# tssop38.net
KiCad netlist of a schematic drawn in EAGLE
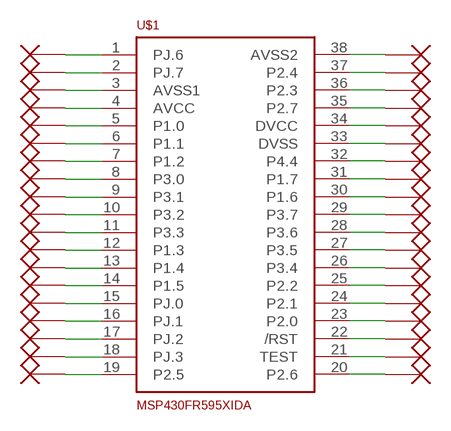
[diagram p0: schematic, sheet 1]

(export (version "E")
  (design (tool "Eeschema 10.0.6"))
  (components
    (comp (ref "P1")
      (value "PIN")
      (footprint "eagle-import:PIN")
      (libsource (lib "eagle-import") (part "PIN"))
    )
    (comp (ref "P2")
      (value "PIN")
      (footprint "eagle-import:PIN")
      (libsource (lib "eagle-import") (part "PIN"))
    )
    (comp (ref "P3")
      (value "PIN")
      (footprint "eagle-import:PIN")
      (libsource (lib "eagle-import") (part "PIN"))
    )
    (comp (ref "P4")
      (value "PIN")
      (footprint "eagle-import:PIN")
      (libsource (lib "eagle-import") (part "PIN"))
    )
    (comp (ref "P5")
      (value "PIN")
      (footprint "eagle-import:PIN")
      (libsource (lib "eagle-import") (part "PIN"))
    )
    (comp (ref "P6")
      (value "PIN")
      (footprint "eagle-import:PIN")
      (libsource (lib "eagle-import") (part "PIN"))
    )
    (comp (ref "P7")
      (value "PIN")
      (footprint "eagle-import:PIN")
      (libsource (lib "eagle-import") (part "PIN"))
    )
    (comp (ref "P8")
      (value "PIN")
      (footprint "eagle-import:PIN")
      (libsource (lib "eagle-import") (part "PIN"))
    )
    (comp (ref "P9")
      (value "PIN")
      (footprint "eagle-import:PIN")
      (libsource (lib "eagle-import") (part "PIN"))
    )
    (comp (ref "P10")
      (value "PIN")
      (footprint "eagle-import:PIN")
      (libsource (lib "eagle-import") (part "PIN"))
    )
    (comp (ref "P11")
      (value "PIN")
      (footprint "eagle-import:PIN")
      (libsource (lib "eagle-import") (part "PIN"))
    )
    (comp (ref "P12")
      (value "PIN")
      (footprint "eagle-import:PIN")
      (libsource (lib "eagle-import") (part "PIN"))
    )
    (comp (ref "P13")
      (value "PIN")
      (footprint "eagle-import:PIN")
      (libsource (lib "eagle-import") (part "PIN"))
    )
    (comp (ref "P14")
      (value "PIN")
      (footprint "eagle-import:PIN")
      (libsource (lib "eagle-import") (part "PIN"))
    )
    (comp (ref "P15")
      (value "PIN")
      (footprint "eagle-import:PIN")
      (libsource (lib "eagle-import") (part "PIN"))
    )
    (comp (ref "P16")
      (value "PIN")
      (footprint "eagle-import:PIN")
      (libsource (lib "eagle-import") (part "PIN"))
    )
    (comp (ref "P17")
      (value "PIN")
      (footprint "eagle-import:PIN")
      (libsource (lib "eagle-import") (part "PIN"))
    )
    (comp (ref "P18")
      (value "PIN")
      (footprint "eagle-import:PIN")
      (libsource (lib "eagle-import") (part "PIN"))
    )
    (comp (ref "P19")
      (value "PIN")
      (footprint "eagle-import:PIN")
      (libsource (lib "eagle-import") (part "PIN"))
    )
    (comp (ref "P20")
      (value "PIN")
      (footprint "eagle-import:PIN")
      (libsource (lib "eagle-import") (part "PIN"))
    )
    (comp (ref "P21")
      (value "PIN")
      (footprint "eagle-import:PIN")
      (libsource (lib "eagle-import") (part "PIN"))
    )
    (comp (ref "P22")
      (value "PIN")
      (footprint "eagle-import:PIN")
      (libsource (lib "eagle-import") (part "PIN"))
    )
    (comp (ref "P23")
      (value "PIN")
      (footprint "eagle-import:PIN")
      (libsource (lib "eagle-import") (part "PIN"))
    )
    (comp (ref "P24")
      (value "PIN")
      (footprint "eagle-import:PIN")
      (libsource (lib "eagle-import") (part "PIN"))
    )
    (comp (ref "P25")
      (value "PIN")
      (footprint "eagle-import:PIN")
      (libsource (lib "eagle-import") (part "PIN"))
    )
    (comp (ref "P26")
      (value "PIN")
      (footprint "eagle-import:PIN")
      (libsource (lib "eagle-import") (part "PIN"))
    )
    (comp (ref "P27")
      (value "PIN")
      (footprint "eagle-import:PIN")
      (libsource (lib "eagle-import") (part "PIN"))
    )
    (comp (ref "P28")
      (value "PIN")
      (footprint "eagle-import:PIN")
      (libsource (lib "eagle-import") (part "PIN"))
    )
    (comp (ref "P29")
      (value "PIN")
      (footprint "eagle-import:PIN")
      (libsource (lib "eagle-import") (part "PIN"))
    )
    (comp (ref "P30")
      (value "PIN")
      (footprint "eagle-import:PIN")
      (libsource (lib "eagle-import") (part "PIN"))
    )
    (comp (ref "P31")
      (value "PIN")
      (footprint "eagle-import:PIN")
      (libsource (lib "eagle-import") (part "PIN"))
    )
    (comp (ref "P32")
      (value "PIN")
      (footprint "eagle-import:PIN")
      (libsource (lib "eagle-import") (part "PIN"))
    )
    (comp (ref "P33")
      (value "PIN")
      (footprint "eagle-import:PIN")
      (libsource (lib "eagle-import") (part "PIN"))
    )
    (comp (ref "P34")
      (value "PIN")
      (footprint "eagle-import:PIN")
      (libsource (lib "eagle-import") (part "PIN"))
    )
    (comp (ref "P35")
      (value "PIN")
      (footprint "eagle-import:PIN")
      (libsource (lib "eagle-import") (part "PIN"))
    )
    (comp (ref "P36")
      (value "PIN")
      (footprint "eagle-import:PIN")
      (libsource (lib "eagle-import") (part "PIN"))
    )
    (comp (ref "P37")
      (value "PIN")
      (footprint "eagle-import:PIN")
      (libsource (lib "eagle-import") (part "PIN"))
    )
    (comp (ref "P38")
      (value "PIN")
      (footprint "eagle-import:PIN")
      (libsource (lib "eagle-import") (part "PIN"))
    )
    (comp (ref "U$1")
      (value "MSP430FR595XIDA")
      (footprint "eagle-import:TSSOP38")
      (libsource (lib "eagle-import") (part "MSP430FR595XIDA"))
    )
  )
  (nets
    (net (code "1") (name "Net-(U$1-AVCC)") (class "Default")
      (node (ref "P4") (pin "P$1") (pinfunction "P$1_P$1") (pintype "bidirectional"))
      (node (ref "U$1") (pin "4") (pinfunction "AVCC_4") (pintype "bidirectional"))
    )
    (net (code "2") (name "Net-(U$1-AVSS1)") (class "Default")
      (node (ref "P3") (pin "P$1") (pinfunction "P$1_P$1") (pintype "bidirectional"))
      (node (ref "U$1") (pin "3") (pinfunction "AVSS1_3") (pintype "bidirectional"))
    )
    (net (code "3") (name "Net-(U$1-AVSS2)") (class "Default")
      (node (ref "P38") (pin "P$1") (pinfunction "P$1_P$1") (pintype "bidirectional"))
      (node (ref "U$1") (pin "38") (pinfunction "AVSS2_38") (pintype "bidirectional"))
    )
    (net (code "4") (name "Net-(U$1-DVCC)") (class "Default")
      (node (ref "P34") (pin "P$1") (pinfunction "P$1_P$1") (pintype "bidirectional"))
      (node (ref "U$1") (pin "34") (pinfunction "DVCC_34") (pintype "bidirectional"))
    )
    (net (code "5") (name "Net-(U$1-DVSS)") (class "Default")
      (node (ref "P33") (pin "P$1") (pinfunction "P$1_P$1") (pintype "bidirectional"))
      (node (ref "U$1") (pin "33") (pinfunction "DVSS_33") (pintype "bidirectional"))
    )
    (net (code "6") (name "Net-(U$1-P1.0)") (class "Default")
      (node (ref "P5") (pin "P$1") (pinfunction "P$1_P$1") (pintype "bidirectional"))
      (node (ref "U$1") (pin "5") (pinfunction "P1.0_5") (pintype "bidirectional"))
    )
    (net (code "7") (name "Net-(U$1-P1.1)") (class "Default")
      (node (ref "P6") (pin "P$1") (pinfunction "P$1_P$1") (pintype "bidirectional"))
      (node (ref "U$1") (pin "6") (pinfunction "P1.1_6") (pintype "bidirectional"))
    )
    (net (code "8") (name "Net-(U$1-P1.2)") (class "Default")
      (node (ref "P7") (pin "P$1") (pinfunction "P$1_P$1") (pintype "bidirectional"))
      (node (ref "U$1") (pin "7") (pinfunction "P1.2_7") (pintype "bidirectional"))
    )
    (net (code "9") (name "Net-(U$1-P1.3)") (class "Default")
      (node (ref "P12") (pin "P$1") (pinfunction "P$1_P$1") (pintype "bidirectional"))
      (node (ref "U$1") (pin "12") (pinfunction "P1.3_12") (pintype "bidirectional"))
    )
    (net (code "10") (name "Net-(U$1-P1.4)") (class "Default")
      (node (ref "P13") (pin "P$1") (pinfunction "P$1_P$1") (pintype "bidirectional"))
      (node (ref "U$1") (pin "13") (pinfunction "P1.4_13") (pintype "bidirectional"))
    )
    (net (code "11") (name "Net-(U$1-P1.5)") (class "Default")
      (node (ref "P14") (pin "P$1") (pinfunction "P$1_P$1") (pintype "bidirectional"))
      (node (ref "U$1") (pin "14") (pinfunction "P1.5_14") (pintype "bidirectional"))
    )
    (net (code "12") (name "Net-(U$1-P1.6)") (class "Default")
      (node (ref "P30") (pin "P$1") (pinfunction "P$1_P$1") (pintype "bidirectional"))
      (node (ref "U$1") (pin "30") (pinfunction "P1.6_30") (pintype "bidirectional"))
    )
    (net (code "13") (name "Net-(U$1-P1.7)") (class "Default")
      (node (ref "P31") (pin "P$1") (pinfunction "P$1_P$1") (pintype "bidirectional"))
      (node (ref "U$1") (pin "31") (pinfunction "P1.7_31") (pintype "bidirectional"))
    )
    (net (code "14") (name "Net-(U$1-P2.0)") (class "Default")
      (node (ref "P23") (pin "P$1") (pinfunction "P$1_P$1") (pintype "bidirectional"))
      (node (ref "U$1") (pin "23") (pinfunction "P2.0_23") (pintype "bidirectional"))
    )
    (net (code "15") (name "Net-(U$1-P2.1)") (class "Default")
      (node (ref "P24") (pin "P$1") (pinfunction "P$1_P$1") (pintype "bidirectional"))
      (node (ref "U$1") (pin "24") (pinfunction "P2.1_24") (pintype "bidirectional"))
    )
    (net (code "16") (name "Net-(U$1-P2.2)") (class "Default")
      (node (ref "P25") (pin "P$1") (pinfunction "P$1_P$1") (pintype "bidirectional"))
      (node (ref "U$1") (pin "25") (pinfunction "P2.2_25") (pintype "bidirectional"))
    )
    (net (code "17") (name "Net-(U$1-P2.3)") (class "Default")
      (node (ref "P36") (pin "P$1") (pinfunction "P$1_P$1") (pintype "bidirectional"))
      (node (ref "U$1") (pin "36") (pinfunction "P2.3_36") (pintype "bidirectional"))
    )
    (net (code "18") (name "Net-(U$1-P2.4)") (class "Default")
      (node (ref "P37") (pin "P$1") (pinfunction "P$1_P$1") (pintype "bidirectional"))
      (node (ref "U$1") (pin "37") (pinfunction "P2.4_37") (pintype "bidirectional"))
    )
    (net (code "19") (name "Net-(U$1-P2.5)") (class "Default")
      (node (ref "P19") (pin "P$1") (pinfunction "P$1_P$1") (pintype "bidirectional"))
      (node (ref "U$1") (pin "19") (pinfunction "P2.5_19") (pintype "bidirectional"))
    )
    (net (code "20") (name "Net-(U$1-P2.6)") (class "Default")
      (node (ref "P20") (pin "P$1") (pinfunction "P$1_P$1") (pintype "bidirectional"))
      (node (ref "U$1") (pin "20") (pinfunction "P2.6_20") (pintype "bidirectional"))
    )
    (net (code "21") (name "Net-(U$1-P2.7)") (class "Default")
      (node (ref "P35") (pin "P$1") (pinfunction "P$1_P$1") (pintype "bidirectional"))
      (node (ref "U$1") (pin "35") (pinfunction "P2.7_35") (pintype "bidirectional"))
    )
    (net (code "22") (name "Net-(U$1-P3.0)") (class "Default")
      (node (ref "P8") (pin "P$1") (pinfunction "P$1_P$1") (pintype "bidirectional"))
      (node (ref "U$1") (pin "8") (pinfunction "P3.0_8") (pintype "bidirectional"))
    )
    (net (code "23") (name "Net-(U$1-P3.1)") (class "Default")
      (node (ref "P9") (pin "P$1") (pinfunction "P$1_P$1") (pintype "bidirectional"))
      (node (ref "U$1") (pin "9") (pinfunction "P3.1_9") (pintype "bidirectional"))
    )
    (net (code "24") (name "Net-(U$1-P3.2)") (class "Default")
      (node (ref "P10") (pin "P$1") (pinfunction "P$1_P$1") (pintype "bidirectional"))
      (node (ref "U$1") (pin "10") (pinfunction "P3.2_10") (pintype "bidirectional"))
    )
    (net (code "25") (name "Net-(U$1-P3.3)") (class "Default")
      (node (ref "P11") (pin "P$1") (pinfunction "P$1_P$1") (pintype "bidirectional"))
      (node (ref "U$1") (pin "11") (pinfunction "P3.3_11") (pintype "bidirectional"))
    )
    (net (code "26") (name "Net-(U$1-P3.4)") (class "Default")
      (node (ref "P26") (pin "P$1") (pinfunction "P$1_P$1") (pintype "bidirectional"))
      (node (ref "U$1") (pin "26") (pinfunction "P3.4_26") (pintype "bidirectional"))
    )
    (net (code "27") (name "Net-(U$1-P3.5)") (class "Default")
      (node (ref "P27") (pin "P$1") (pinfunction "P$1_P$1") (pintype "bidirectional"))
      (node (ref "U$1") (pin "27") (pinfunction "P3.5_27") (pintype "bidirectional"))
    )
    (net (code "28") (name "Net-(U$1-P3.6)") (class "Default")
      (node (ref "P28") (pin "P$1") (pinfunction "P$1_P$1") (pintype "bidirectional"))
      (node (ref "U$1") (pin "28") (pinfunction "P3.6_28") (pintype "bidirectional"))
    )
    (net (code "29") (name "Net-(U$1-P3.7)") (class "Default")
      (node (ref "P29") (pin "P$1") (pinfunction "P$1_P$1") (pintype "bidirectional"))
      (node (ref "U$1") (pin "29") (pinfunction "P3.7_29") (pintype "bidirectional"))
    )
    (net (code "30") (name "Net-(U$1-P4.4)") (class "Default")
      (node (ref "P32") (pin "P$1") (pinfunction "P$1_P$1") (pintype "bidirectional"))
      (node (ref "U$1") (pin "32") (pinfunction "P4.4_32") (pintype "bidirectional"))
    )
    (net (code "31") (name "Net-(U$1-PJ.0)") (class "Default")
      (node (ref "P15") (pin "P$1") (pinfunction "P$1_P$1") (pintype "bidirectional"))
      (node (ref "U$1") (pin "15") (pinfunction "PJ.0_15") (pintype "bidirectional"))
    )
    (net (code "32") (name "Net-(U$1-PJ.1)") (class "Default")
      (node (ref "P16") (pin "P$1") (pinfunction "P$1_P$1") (pintype "bidirectional"))
      (node (ref "U$1") (pin "16") (pinfunction "PJ.1_16") (pintype "bidirectional"))
    )
    (net (code "33") (name "Net-(U$1-PJ.2)") (class "Default")
      (node (ref "P17") (pin "P$1") (pinfunction "P$1_P$1") (pintype "bidirectional"))
      (node (ref "U$1") (pin "17") (pinfunction "PJ.2_17") (pintype "bidirectional"))
    )
    (net (code "34") (name "Net-(U$1-PJ.3)") (class "Default")
      (node (ref "P18") (pin "P$1") (pinfunction "P$1_P$1") (pintype "bidirectional"))
      (node (ref "U$1") (pin "18") (pinfunction "PJ.3_18") (pintype "bidirectional"))
    )
    (net (code "35") (name "Net-(U$1-PJ.6)") (class "Default")
      (node (ref "P1") (pin "P$1") (pinfunction "P$1_P$1") (pintype "bidirectional"))
      (node (ref "U$1") (pin "1") (pinfunction "PJ.6_1") (pintype "bidirectional"))
    )
    (net (code "36") (name "Net-(U$1-PJ.7)") (class "Default")
      (node (ref "P2") (pin "P$1") (pinfunction "P$1_P$1") (pintype "bidirectional"))
      (node (ref "U$1") (pin "2") (pinfunction "PJ.7_2") (pintype "bidirectional"))
    )
    (net (code "37") (name "Net-(U$1-TEST)") (class "Default")
      (node (ref "P21") (pin "P$1") (pinfunction "P$1_P$1") (pintype "bidirectional"))
      (node (ref "U$1") (pin "21") (pinfunction "TEST_21") (pintype "bidirectional"))
    )
    (net (code "38") (name "Net-(U$1-{slash}RST)") (class "Default")
      (node (ref "P22") (pin "P$1") (pinfunction "P$1_P$1") (pintype "bidirectional"))
      (node (ref "U$1") (pin "22") (pinfunction "/RST_22") (pintype "bidirectional"))
    )
  )
)
